# 7segement3digits1badidea-mk-1_0.net
KiCad netlist of a schematic drawn in EAGLE
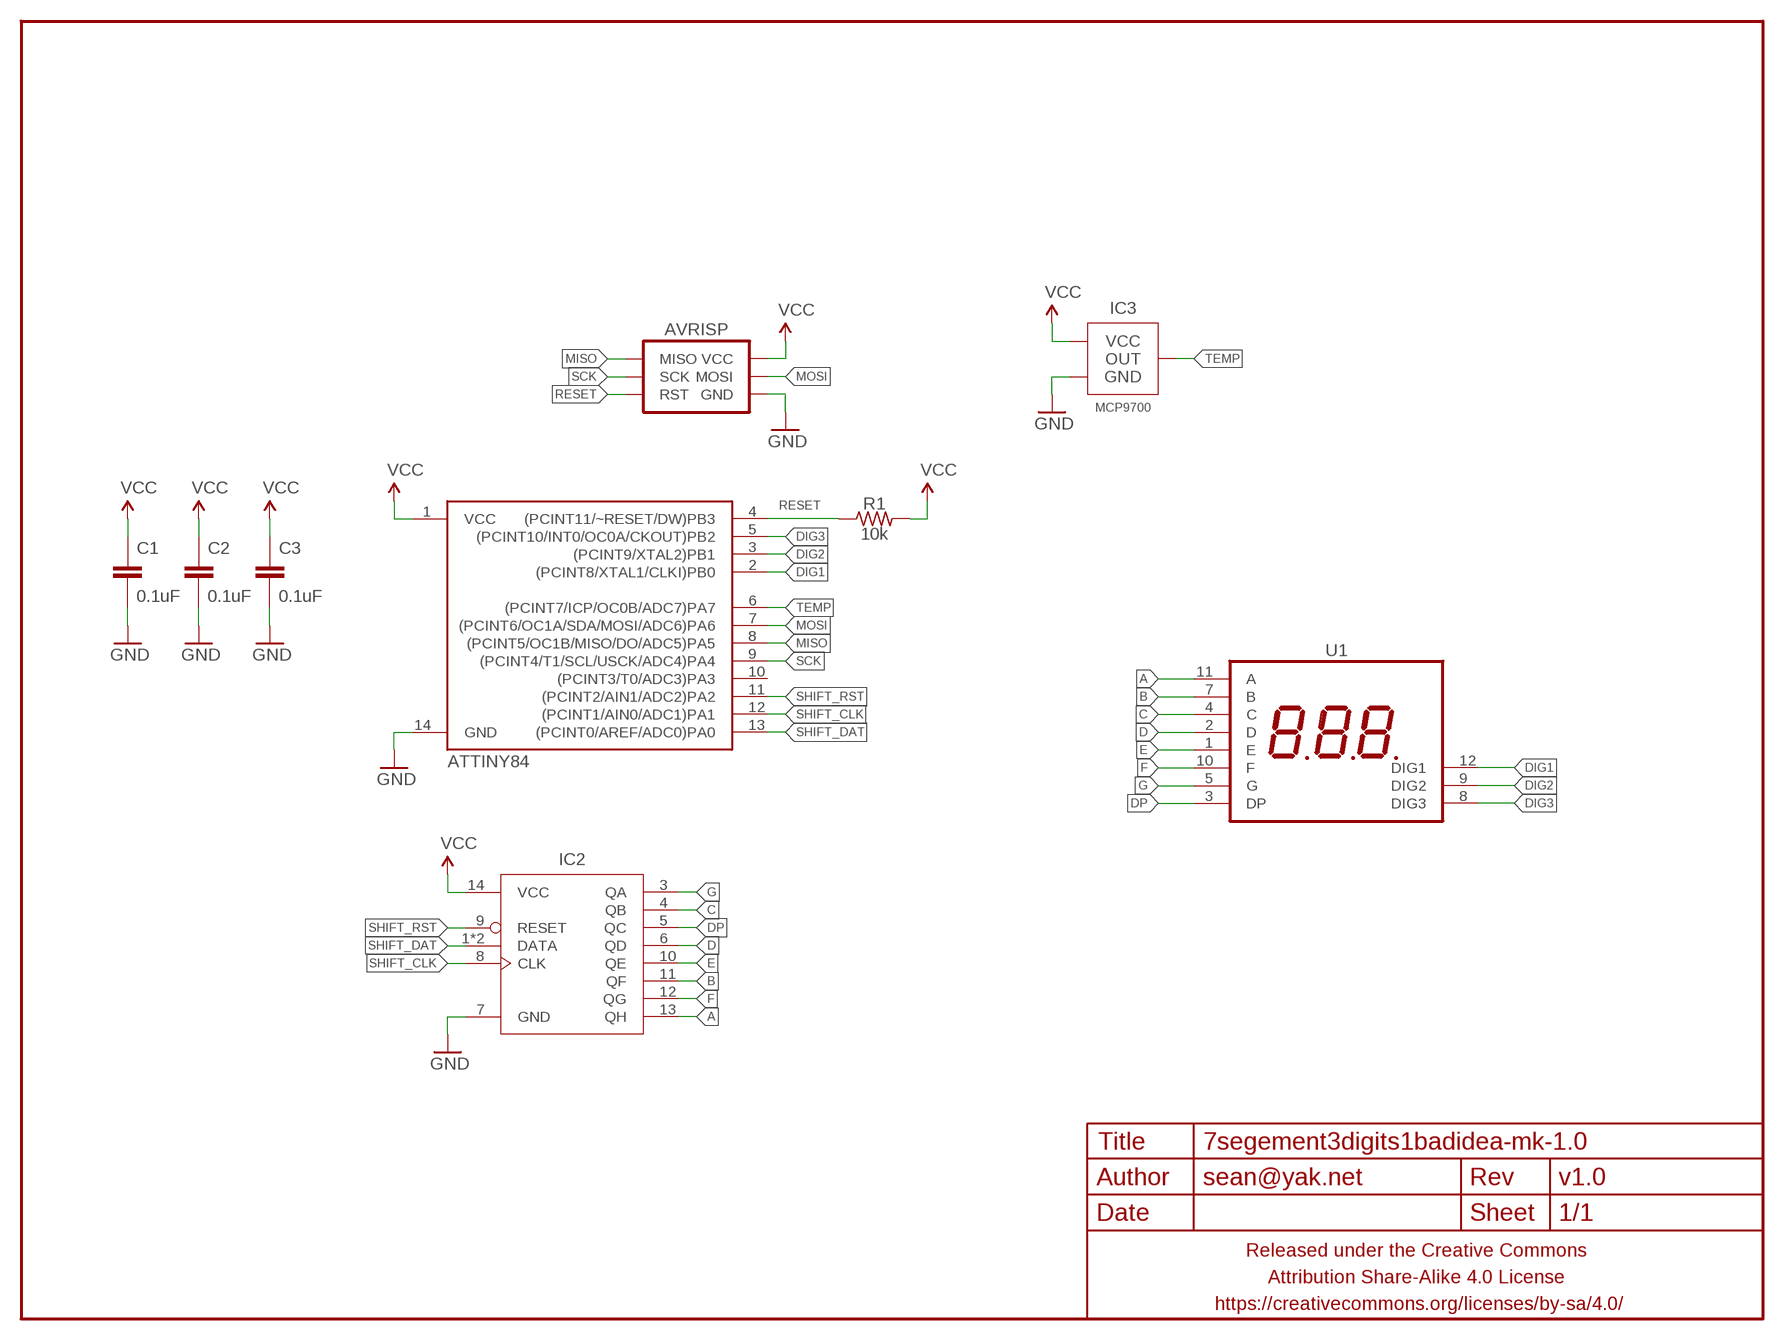
[diagram p0: schematic, sheet 1]

(export (version "E")
  (design (tool "Eeschema 10.0.6"))
  (components
    (comp (ref "AVRISP")
      (value "AVR_SPI_PRG_6PTH_INLINE_I2C")
      (footprint "eagle-import:AVR_ISP_INLINE_PTH_I2C")
      (libsource (lib "eagle-import") (part "AVR_SPI_PRG_6PTH_INLINE_I2C"))
    )
    (comp (ref "C1")
      (value "0.1uF")
      (footprint "eagle-import:C0603")
      (libsource (lib "eagle-import") (part "CAPACITOR-CERAMICC0603"))
    )
    (comp (ref "C2")
      (value "0.1uF")
      (footprint "eagle-import:C0603")
      (libsource (lib "eagle-import") (part "CAPACITOR-CERAMICC0603"))
    )
    (comp (ref "C3")
      (value "0.1uF")
      (footprint "eagle-import:C0603")
      (libsource (lib "eagle-import") (part "CAPACITOR-CERAMICC0603"))
    )
    (comp (ref "FRAME1")
      (value "FRAME-LETTERNO_PACKAGE")
      (footprint "eagle-import:DUMMY")
      (fields (field (name "DESIGNER") "sean@yak.net") (field (name "VERSION") "v1.0"))
      (libsource (lib "eagle-import") (part "FRAME-LETTERNO_PACKAGE"))
    )
    (comp (ref "IC1")
      (value "ATTINY84")
      (footprint "eagle-import:SO14")
      (libsource (lib "eagle-import") (part "ATTINY84"))
    )
    (comp (ref "IC2")
      (value "74HC164")
      (footprint "eagle-import:SO14")
      (libsource (lib "eagle-import") (part "74164SOIC"))
    )
    (comp (ref "IC3")
      (value "MCP9700")
      (footprint "eagle-import:SOT23")
      (libsource (lib "eagle-import") (part "MCP9700SOT23"))
    )
    (comp (ref "R1")
      (value "10k")
      (footprint "eagle-import:R0603")
      (libsource (lib "eagle-import") (part "RESISTORR0603"))
    )
    (comp (ref "U1")
      (value "7SEG_3DIGIT")
      (footprint "eagle-import:7SEG_3DIG_0.56IN")
      (libsource (lib "eagle-import") (part "7SEG_3DIGIT"))
    )
  )
  (nets
    (net (code "1") (name "A") (class "Default")
      (node (ref "IC2") (pin "13") (pinfunction "QH_13") (pintype "bidirectional"))
      (node (ref "U1") (pin "11") (pinfunction "A_11") (pintype "passive"))
    )
    (net (code "2") (name "B") (class "Default")
      (node (ref "IC2") (pin "11") (pinfunction "QF_11") (pintype "bidirectional"))
      (node (ref "U1") (pin "7") (pinfunction "B_7") (pintype "passive"))
    )
    (net (code "3") (name "C") (class "Default")
      (node (ref "IC2") (pin "4") (pinfunction "QB_4") (pintype "bidirectional"))
      (node (ref "U1") (pin "4") (pinfunction "C_4") (pintype "passive"))
    )
    (net (code "4") (name "D") (class "Default")
      (node (ref "IC2") (pin "6") (pinfunction "QD_6") (pintype "bidirectional"))
      (node (ref "U1") (pin "2") (pinfunction "D_2") (pintype "passive"))
    )
    (net (code "5") (name "DIG1") (class "Default")
      (node (ref "IC1") (pin "2") (pinfunction "(PCINT8/XTAL1/CLKI)PB0_2") (pintype "bidirectional"))
      (node (ref "U1") (pin "12") (pinfunction "DIG1_12") (pintype "passive"))
    )
    (net (code "6") (name "DIG2") (class "Default")
      (node (ref "IC1") (pin "3") (pinfunction "(PCINT9/XTAL2)PB1_3") (pintype "bidirectional"))
      (node (ref "U1") (pin "9") (pinfunction "DIG2_9") (pintype "passive"))
    )
    (net (code "7") (name "DIG3") (class "Default")
      (node (ref "IC1") (pin "5") (pinfunction "(PCINT10/INT0/OC0A/CKOUT)PB2_5") (pintype "bidirectional"))
      (node (ref "U1") (pin "8") (pinfunction "DIG3_8") (pintype "passive"))
    )
    (net (code "8") (name "DP") (class "Default")
      (node (ref "IC2") (pin "5") (pinfunction "QC_5") (pintype "bidirectional"))
      (node (ref "U1") (pin "3") (pinfunction "DP_3") (pintype "passive"))
    )
    (net (code "9") (name "E") (class "Default")
      (node (ref "IC2") (pin "10") (pinfunction "QE_10") (pintype "bidirectional"))
      (node (ref "U1") (pin "1") (pinfunction "E_1") (pintype "passive"))
    )
    (net (code "10") (name "F") (class "Default")
      (node (ref "IC2") (pin "12") (pinfunction "QG_12") (pintype "bidirectional"))
      (node (ref "U1") (pin "10") (pinfunction "F_10") (pintype "passive"))
    )
    (net (code "11") (name "G") (class "Default")
      (node (ref "IC2") (pin "3") (pinfunction "QA_3") (pintype "bidirectional"))
      (node (ref "U1") (pin "5") (pinfunction "G_5") (pintype "passive"))
    )
    (net (code "12") (name "GND") (class "Default")
      (node (ref "AVRISP") (pin "GND") (pinfunction "GND_GND") (pintype "passive"))
      (node (ref "C1") (pin "2") (pinfunction "2_2") (pintype "passive"))
      (node (ref "C2") (pin "2") (pinfunction "2_2") (pintype "passive"))
      (node (ref "C3") (pin "2") (pinfunction "2_2") (pintype "passive"))
      (node (ref "IC1") (pin "14") (pinfunction "GND_14") (pintype "bidirectional"))
      (node (ref "IC2") (pin "7") (pinfunction "GND_7") (pintype "bidirectional"))
      (node (ref "IC3") (pin "3") (pinfunction "GND_3") (pintype "bidirectional"))
    )
    (net (code "13") (name "MISO") (class "Default")
      (node (ref "AVRISP") (pin "MISO") (pinfunction "MISO_MISO") (pintype "passive"))
      (node (ref "IC1") (pin "8") (pinfunction "(PCINT5/OC1B/MISO/DO/ADC5)PA5_8") (pintype "bidirectional"))
    )
    (net (code "14") (name "MOSI") (class "Default")
      (node (ref "AVRISP") (pin "MOSI") (pinfunction "MOSI_MOSI") (pintype "passive"))
      (node (ref "IC1") (pin "7") (pinfunction "(PCINT6/OC1A/SDA/MOSI/ADC6)PA6_7") (pintype "bidirectional"))
    )
    (net (code "15") (name "RESET") (class "Default")
      (node (ref "AVRISP") (pin "RESET") (pinfunction "RST_RESET") (pintype "passive"))
      (node (ref "IC1") (pin "4") (pinfunction "(PCINT11/~{RESET/DW})PB3_4") (pintype "bidirectional"))
      (node (ref "R1") (pin "1") (pinfunction "1_1") (pintype "passive"))
    )
    (net (code "16") (name "SCK") (class "Default")
      (node (ref "AVRISP") (pin "SCK") (pinfunction "SCK_SCK") (pintype "passive"))
      (node (ref "IC1") (pin "9") (pinfunction "(PCINT4/T1/SCL/USCK/ADC4)PA4_9") (pintype "bidirectional"))
    )
    (net (code "17") (name "SHIFT_CLK") (class "Default")
      (node (ref "IC1") (pin "12") (pinfunction "(PCINT1/AIN0/ADC1)PA1_12") (pintype "bidirectional"))
      (node (ref "IC2") (pin "8") (pinfunction "CLK_8") (pintype "bidirectional"))
    )
    (net (code "18") (name "SHIFT_DAT") (class "Default")
      (node (ref "IC1") (pin "13") (pinfunction "(PCINT0/AREF/ADC0)PA0_13") (pintype "bidirectional"))
      (node (ref "IC2") (pin "1") (pinfunction "DATA_1") (pintype "bidirectional"))
      (node (ref "IC2") (pin "2") (pinfunction "DATA_2") (pintype "bidirectional"))
    )
    (net (code "19") (name "SHIFT_RST") (class "Default")
      (node (ref "IC1") (pin "11") (pinfunction "(PCINT2/AIN1/ADC2)PA2_11") (pintype "bidirectional"))
      (node (ref "IC2") (pin "9") (pinfunction "RESET_9") (pintype "bidirectional"))
    )
    (net (code "20") (name "TEMP") (class "Default")
      (node (ref "IC1") (pin "6") (pinfunction "(PCINT7/ICP/OC0B/ADC7)PA7_6") (pintype "bidirectional"))
      (node (ref "IC3") (pin "2") (pinfunction "OUT_2") (pintype "bidirectional"))
    )
    (net (code "21") (name "VCC") (class "Default")
      (node (ref "AVRISP") (pin "VCC") (pinfunction "VCC_VCC") (pintype "passive"))
      (node (ref "C1") (pin "1") (pinfunction "1_1") (pintype "passive"))
      (node (ref "C2") (pin "1") (pinfunction "1_1") (pintype "passive"))
      (node (ref "C3") (pin "1") (pinfunction "1_1") (pintype "passive"))
      (node (ref "IC1") (pin "1") (pinfunction "VCC_1") (pintype "bidirectional"))
      (node (ref "IC2") (pin "14") (pinfunction "VCC_14") (pintype "bidirectional"))
      (node (ref "IC3") (pin "1") (pinfunction "VCC_1") (pintype "bidirectional"))
      (node (ref "R1") (pin "2") (pinfunction "2_2") (pintype "passive"))
    )
    (net (code "22") (name "unconnected-(IC1-(PCINT3{slash}T0{slash}ADC3)PA3-Pad10)") (class "Default")
      (node (ref "IC1") (pin "10") (pinfunction "(PCINT3/T0/ADC3)PA3_10") (pintype "bidirectional"))
    )
  )
)
